# 4069-Twin-T-Drums-PinConn-alt.net
KiCad netlist of a schematic drawn in EAGLE
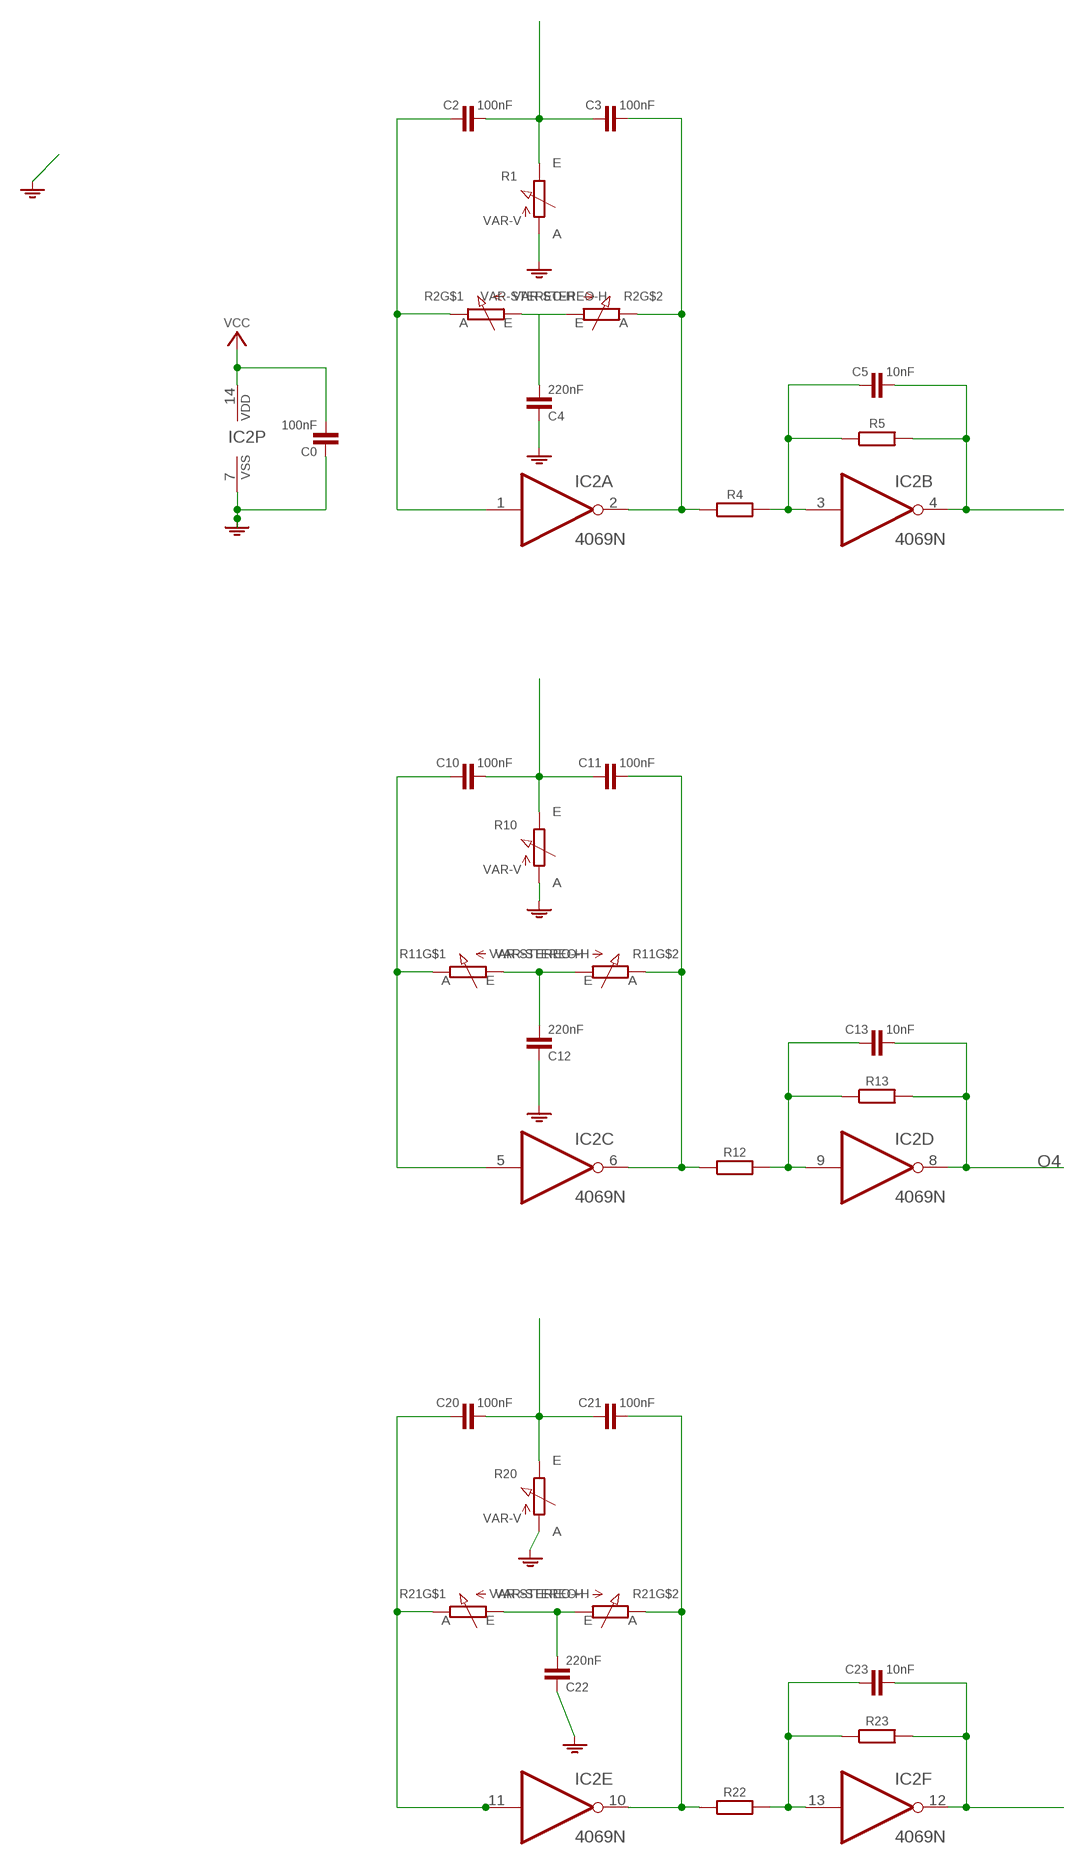
[diagram p0: schematic, sheet 1]

(export (version "E")
  (design (tool "Eeschema 10.0.6"))
  (components
    (comp (ref "C0")
      (value "100nF")
      (footprint "eagle-import:C050-020X044_V")
      (libsource (lib "eagle-import") (part "C050-020X044/V"))
    )
    (comp (ref "C2")
      (value "100nF")
      (footprint "eagle-import:C050-020X044")
      (libsource (lib "eagle-import") (part "C-H050-020X044"))
    )
    (comp (ref "C3")
      (value "100nF")
      (footprint "eagle-import:C050-020X044")
      (libsource (lib "eagle-import") (part "C-H050-020X044"))
    )
    (comp (ref "C4")
      (value "220nF")
      (footprint "eagle-import:C050-020X044_V")
      (libsource (lib "eagle-import") (part "C050-020X044/V"))
    )
    (comp (ref "C5")
      (value "10nF")
      (footprint "eagle-import:C025-015X024")
      (libsource (lib "eagle-import") (part "C-H025-015X024"))
    )
    (comp (ref "C10")
      (value "100nF")
      (footprint "eagle-import:C050-020X044")
      (libsource (lib "eagle-import") (part "C-H050-020X044"))
    )
    (comp (ref "C11")
      (value "100nF")
      (footprint "eagle-import:C050-020X044")
      (libsource (lib "eagle-import") (part "C-H050-020X044"))
    )
    (comp (ref "C12")
      (value "220nF")
      (footprint "eagle-import:C050-020X044_V")
      (libsource (lib "eagle-import") (part "C050-020X044/V"))
    )
    (comp (ref "C13")
      (value "10nF")
      (footprint "eagle-import:C025-015X024")
      (libsource (lib "eagle-import") (part "C-H025-015X024"))
    )
    (comp (ref "C20")
      (value "100nF")
      (footprint "eagle-import:C050-020X044")
      (libsource (lib "eagle-import") (part "C-H050-020X044"))
    )
    (comp (ref "C21")
      (value "100nF")
      (footprint "eagle-import:C050-020X044")
      (libsource (lib "eagle-import") (part "C-H050-020X044"))
    )
    (comp (ref "C22")
      (value "220nF")
      (footprint "eagle-import:C050-020X044_V")
      (libsource (lib "eagle-import") (part "C050-020X044/V"))
    )
    (comp (ref "C23")
      (value "10nF")
      (footprint "eagle-import:C025-015X024")
      (libsource (lib "eagle-import") (part "C-H025-015X024"))
    )
    (comp (ref "IC2")
      (value "4069N")
      (footprint "eagle-import:DIL14")
      (libsource (lib "eagle-import") (part "4069N"))
    )
    (comp (ref "R1")
      (value "VAR-V")
      (footprint "eagle-import:CONN-2P")
      (libsource (lib "eagle-import") (part "VAR-V"))
    )
    (comp (ref "R2")
      (value "VAR-STEREO-H")
      (footprint "eagle-import:CONN-2X2")
      (libsource (lib "eagle-import") (part "VAR-STEREO-H"))
    )
    (comp (ref "R4")
      (value "R-H0202/2V")
      (footprint "eagle-import:0202_2V")
      (libsource (lib "eagle-import") (part "R-H0202/2V"))
    )
    (comp (ref "R5")
      (value "R-H0202/2V")
      (footprint "eagle-import:0202_2V")
      (libsource (lib "eagle-import") (part "R-H0202/2V"))
    )
    (comp (ref "R10")
      (value "VAR-V")
      (footprint "eagle-import:CONN-2P")
      (libsource (lib "eagle-import") (part "VAR-V"))
    )
    (comp (ref "R11")
      (value "VAR-STEREO-H")
      (footprint "eagle-import:CONN-2X2")
      (libsource (lib "eagle-import") (part "VAR-STEREO-H"))
    )
    (comp (ref "R12")
      (value "R-H0204/10")
      (footprint "eagle-import:0204_10")
      (libsource (lib "eagle-import") (part "R-H0204/10"))
    )
    (comp (ref "R13")
      (value "R-H0202/2V")
      (footprint "eagle-import:0202_2V")
      (libsource (lib "eagle-import") (part "R-H0202/2V"))
    )
    (comp (ref "R20")
      (value "VAR-V")
      (footprint "eagle-import:CONN-2P")
      (libsource (lib "eagle-import") (part "VAR-V"))
    )
    (comp (ref "R21")
      (value "VAR-STEREO-H")
      (footprint "eagle-import:CONN-2X2")
      (libsource (lib "eagle-import") (part "VAR-STEREO-H"))
    )
    (comp (ref "R22")
      (value "R-H0204/10-V")
      (footprint "eagle-import:0204_10-V")
      (libsource (lib "eagle-import") (part "R-H0204/10-V"))
    )
    (comp (ref "R23")
      (value "R-H0202/2V")
      (footprint "eagle-import:0202_2V")
      (libsource (lib "eagle-import") (part "R-H0202/2V"))
    )
    (comp (ref "S12")
      (value "VCC_GNDPWR-L")
      (footprint "eagle-import:PWR-L")
      (libsource (lib "eagle-import") (part "VCC_GNDPWR-L"))
    )
  )
  (nets
    (net (code "1") (name "/O4") (class "Default")
      (node (ref "C13") (pin "2") (pinfunction "2_2") (pintype "passive"))
      (node (ref "IC2") (pin "8") (pinfunction "O_8") (pintype "output"))
      (node (ref "R13") (pin "2") (pinfunction "2_2") (pintype "passive"))
    )
    (net (code "2") (name "GND") (class "Default")
      (node (ref "C0") (pin "1") (pinfunction "1_1") (pintype "passive"))
      (node (ref "C12") (pin "1") (pinfunction "1_1") (pintype "passive"))
      (node (ref "C22") (pin "1") (pinfunction "1_1") (pintype "passive"))
      (node (ref "C4") (pin "1") (pinfunction "1_1") (pintype "passive"))
      (node (ref "IC2") (pin "7") (pinfunction "VSS_7") (pintype "power_in"))
      (node (ref "R1") (pin "1") (pinfunction "A_1") (pintype "passive"))
      (node (ref "R10") (pin "1") (pinfunction "A_1") (pintype "passive"))
      (node (ref "R20") (pin "1") (pinfunction "A_1") (pintype "passive"))
      (node (ref "S12") (pin "1") (pinfunction "GND_1") (pintype "power_in"))
    )
    (net (code "3") (name "Net-(IC2A-I)") (class "Default")
      (node (ref "C2") (pin "1") (pinfunction "1_1") (pintype "passive"))
      (node (ref "IC2") (pin "1") (pinfunction "I_1") (pintype "input"))
      (node (ref "R2") (pin "2") (pinfunction "S-A_2") (pintype "passive"))
    )
    (net (code "4") (name "Net-(IC2A-O)") (class "Default")
      (node (ref "C3") (pin "2") (pinfunction "2_2") (pintype "passive"))
      (node (ref "IC2") (pin "2") (pinfunction "O_2") (pintype "output"))
      (node (ref "R2") (pin "4") (pinfunction "S-A_4") (pintype "passive"))
      (node (ref "R4") (pin "1") (pinfunction "1_1") (pintype "passive"))
    )
    (net (code "5") (name "Net-(IC2B-I)") (class "Default")
      (node (ref "C5") (pin "1") (pinfunction "1_1") (pintype "passive"))
      (node (ref "IC2") (pin "3") (pinfunction "I_3") (pintype "input"))
      (node (ref "R4") (pin "2") (pinfunction "2_2") (pintype "passive"))
      (node (ref "R5") (pin "1") (pinfunction "1_1") (pintype "passive"))
    )
    (net (code "6") (name "Net-(IC2B-O)") (class "Default")
      (node (ref "C5") (pin "2") (pinfunction "2_2") (pintype "passive"))
      (node (ref "IC2") (pin "4") (pinfunction "O_4") (pintype "output"))
      (node (ref "R5") (pin "2") (pinfunction "2_2") (pintype "passive"))
    )
    (net (code "7") (name "Net-(IC2C-I)") (class "Default")
      (node (ref "C10") (pin "1") (pinfunction "1_1") (pintype "passive"))
      (node (ref "IC2") (pin "5") (pinfunction "I_5") (pintype "input"))
      (node (ref "R11") (pin "2") (pinfunction "S-A_2") (pintype "passive"))
    )
    (net (code "8") (name "Net-(IC2C-O)") (class "Default")
      (node (ref "C11") (pin "2") (pinfunction "2_2") (pintype "passive"))
      (node (ref "IC2") (pin "6") (pinfunction "O_6") (pintype "output"))
      (node (ref "R11") (pin "4") (pinfunction "S-A_4") (pintype "passive"))
      (node (ref "R12") (pin "1") (pinfunction "1_1") (pintype "passive"))
    )
    (net (code "9") (name "Net-(IC2D-I)") (class "Default")
      (node (ref "C13") (pin "1") (pinfunction "1_1") (pintype "passive"))
      (node (ref "IC2") (pin "9") (pinfunction "I_9") (pintype "input"))
      (node (ref "R12") (pin "2") (pinfunction "2_2") (pintype "passive"))
      (node (ref "R13") (pin "1") (pinfunction "1_1") (pintype "passive"))
    )
    (net (code "10") (name "Net-(IC2E-I)") (class "Default")
      (node (ref "C20") (pin "1") (pinfunction "1_1") (pintype "passive"))
      (node (ref "IC2") (pin "11") (pinfunction "I_11") (pintype "input"))
      (node (ref "R21") (pin "2") (pinfunction "S-A_2") (pintype "passive"))
    )
    (net (code "11") (name "Net-(IC2E-O)") (class "Default")
      (node (ref "C21") (pin "2") (pinfunction "2_2") (pintype "passive"))
      (node (ref "IC2") (pin "10") (pinfunction "O_10") (pintype "output"))
      (node (ref "R21") (pin "4") (pinfunction "S-A_4") (pintype "passive"))
      (node (ref "R22") (pin "1") (pinfunction "1_1") (pintype "passive"))
    )
    (net (code "12") (name "Net-(IC2F-I)") (class "Default")
      (node (ref "C23") (pin "1") (pinfunction "1_1") (pintype "passive"))
      (node (ref "IC2") (pin "13") (pinfunction "I_13") (pintype "input"))
      (node (ref "R22") (pin "2") (pinfunction "2_2") (pintype "passive"))
      (node (ref "R23") (pin "1") (pinfunction "1_1") (pintype "passive"))
    )
    (net (code "13") (name "Net-(IC2F-O)") (class "Default")
      (node (ref "C23") (pin "2") (pinfunction "2_2") (pintype "passive"))
      (node (ref "IC2") (pin "12") (pinfunction "O_12") (pintype "output"))
      (node (ref "R23") (pin "2") (pinfunction "2_2") (pintype "passive"))
    )
    (net (code "14") (name "Net-(IC2G-VDD)") (class "Default")
      (node (ref "C0") (pin "2") (pinfunction "2_2") (pintype "passive"))
      (node (ref "IC2") (pin "14") (pinfunction "VDD_14") (pintype "power_in"))
      (node (ref "S12") (pin "2") (pinfunction "VCC_2") (pintype "power_in"))
    )
    (net (code "15") (name "Net-(R1-S-E)") (class "Default")
      (node (ref "C2") (pin "2") (pinfunction "2_2") (pintype "passive"))
      (node (ref "C3") (pin "1") (pinfunction "1_1") (pintype "passive"))
      (node (ref "R1") (pin "2") (pinfunction "S-E_2") (pintype "passive"))
    )
    (net (code "16") (name "Net-(R2A-A)") (class "Default")
      (node (ref "C4") (pin "2") (pinfunction "2_2") (pintype "passive"))
      (node (ref "R2") (pin "1") (pinfunction "A_1") (pintype "passive"))
      (node (ref "R2") (pin "3") (pinfunction "A_3") (pintype "passive"))
    )
    (net (code "17") (name "Net-(R10-S-E)") (class "Default")
      (node (ref "C10") (pin "2") (pinfunction "2_2") (pintype "passive"))
      (node (ref "C11") (pin "1") (pinfunction "1_1") (pintype "passive"))
      (node (ref "R10") (pin "2") (pinfunction "S-E_2") (pintype "passive"))
    )
    (net (code "18") (name "Net-(R11A-A)") (class "Default")
      (node (ref "C12") (pin "2") (pinfunction "2_2") (pintype "passive"))
      (node (ref "R11") (pin "1") (pinfunction "A_1") (pintype "passive"))
      (node (ref "R11") (pin "3") (pinfunction "A_3") (pintype "passive"))
    )
    (net (code "19") (name "Net-(R20-S-E)") (class "Default")
      (node (ref "C20") (pin "2") (pinfunction "2_2") (pintype "passive"))
      (node (ref "C21") (pin "1") (pinfunction "1_1") (pintype "passive"))
      (node (ref "R20") (pin "2") (pinfunction "S-E_2") (pintype "passive"))
    )
    (net (code "20") (name "Net-(R21A-A)") (class "Default")
      (node (ref "C22") (pin "2") (pinfunction "2_2") (pintype "passive"))
      (node (ref "R21") (pin "1") (pinfunction "A_1") (pintype "passive"))
      (node (ref "R21") (pin "3") (pinfunction "A_3") (pintype "passive"))
    )
  )
)
